# SCHEMATICS.net
KiCad netlist of a schematic drawn in Altium Designer
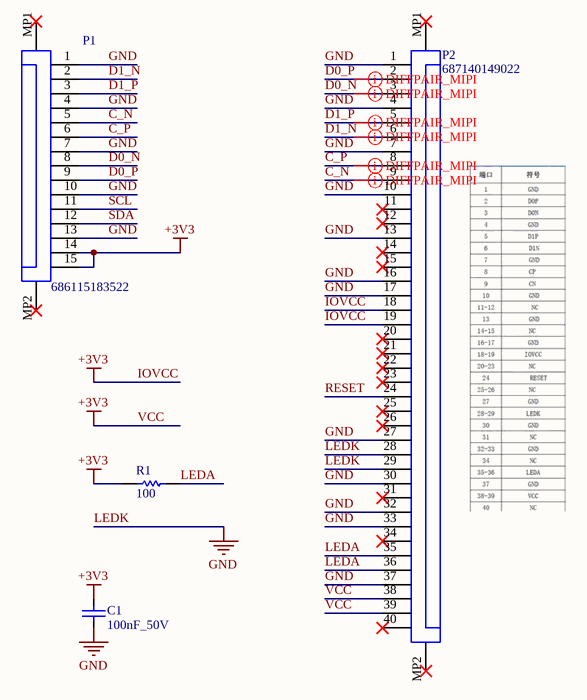
[diagram p0: SCHEMATICS.SchDoc]

(export (version "E")
  (design (tool "Eeschema 10.0.6"))
  (components
    (comp (ref "C1")
      (value "100nF_50V")
      (footprint "CustomLib-Package:C0805")
      (description "50V 100nF X7R ±10% 0805 Multilayer Ceramic Capacitors MLCC - SMD/SMT ROHS")
      (fields (field (name "MANUFACTURER") "YAGEO") (field (name "Comment") "CC0805KRX7R9BB104"))
      (libsource (lib "CustomLib-Package") (part "CAPACITOR"))
    )
    (comp (ref "P1")
      (value "686115183522")
      (footprint "686115183522")
      (description "15 Position FFC, FPC Connector Contacts, Bottom 1.0mm Surface Mount, Right Angle")
      (libsource (lib "CustomLib-Package") (part "CON-FPC-1MM-15P-RA"))
    )
    (comp (ref "P2")
      (value "687140149022")
      (footprint "687140149022")
      (description "40 Position FFC, FPC Connector Contacts, Bottom 0.020 (0.50mm) Surface Mount, Right Angle")
      (libsource (lib "CustomLib-Package") (part "CON-FPC-0.5MM-40P-RA"))
    )
    (comp (ref "R1")
      (value "100")
      (footprint "CustomLib-Package:R0805")
      (fields (field (name "MANUFACTURER") "YAGEO") (field (name "Comment") "AC0805FR-07100RL"))
      (libsource (lib "CustomLib-Package") (part "RESISTOR"))
    )
  )
  (nets
    (net (code "1") (name "+3V3") (class "Default")
      (node (ref "C1") (pin "1") (pinfunction "1_1") (pintype "passive"))
      (node (ref "P1") (pin "14") (pinfunction "14_14") (pintype "passive"))
      (node (ref "P1") (pin "15") (pinfunction "15_15") (pintype "passive"))
      (node (ref "P2") (pin "18") (pinfunction "18_18") (pintype "passive"))
      (node (ref "P2") (pin "19") (pinfunction "19_19") (pintype "passive"))
      (node (ref "P2") (pin "38") (pinfunction "38_38") (pintype "passive"))
      (node (ref "P2") (pin "39") (pinfunction "39_39") (pintype "passive"))
      (node (ref "R1") (pin "2") (pinfunction "2_2") (pintype "passive"))
    )
    (net (code "2") (name "/C_N") (class "Default")
      (node (ref "P1") (pin "5") (pinfunction "5_5") (pintype "passive"))
      (node (ref "P2") (pin "9") (pinfunction "9_9") (pintype "passive"))
    )
    (net (code "3") (name "/C_P") (class "Default")
      (node (ref "P1") (pin "6") (pinfunction "6_6") (pintype "passive"))
      (node (ref "P2") (pin "8") (pinfunction "8_8") (pintype "passive"))
    )
    (net (code "4") (name "/D0_N") (class "Default")
      (node (ref "P1") (pin "8") (pinfunction "8_8") (pintype "passive"))
      (node (ref "P2") (pin "3") (pinfunction "3_3") (pintype "passive"))
    )
    (net (code "5") (name "/D0_P") (class "Default")
      (node (ref "P1") (pin "9") (pinfunction "9_9") (pintype "passive"))
      (node (ref "P2") (pin "2") (pinfunction "2_2") (pintype "passive"))
    )
    (net (code "6") (name "/D1_N") (class "Default")
      (node (ref "P1") (pin "2") (pinfunction "2_2") (pintype "passive"))
      (node (ref "P2") (pin "6") (pinfunction "6_6") (pintype "passive"))
    )
    (net (code "7") (name "/D1_P") (class "Default")
      (node (ref "P1") (pin "3") (pinfunction "3_3") (pintype "passive"))
      (node (ref "P2") (pin "5") (pinfunction "5_5") (pintype "passive"))
    )
    (net (code "8") (name "/LEDA") (class "Default")
      (node (ref "P2") (pin "35") (pinfunction "35_35") (pintype "passive"))
      (node (ref "P2") (pin "36") (pinfunction "36_36") (pintype "passive"))
      (node (ref "R1") (pin "1") (pinfunction "1_1") (pintype "passive"))
    )
    (net (code "9") (name "/RESET") (class "Default")
      (node (ref "P2") (pin "24") (pinfunction "24_24") (pintype "passive"))
    )
    (net (code "10") (name "/SCL") (class "Default")
      (node (ref "P1") (pin "11") (pinfunction "11_11") (pintype "passive"))
    )
    (net (code "11") (name "/SDA") (class "Default")
      (node (ref "P1") (pin "12") (pinfunction "12_12") (pintype "passive"))
    )
    (net (code "12") (name "GND") (class "Default")
      (node (ref "C1") (pin "2") (pinfunction "2_2") (pintype "passive"))
      (node (ref "P1") (pin "1") (pinfunction "1_1") (pintype "passive"))
      (node (ref "P1") (pin "10") (pinfunction "10_10") (pintype "passive"))
      (node (ref "P1") (pin "13") (pinfunction "13_13") (pintype "passive"))
      (node (ref "P1") (pin "4") (pinfunction "4_4") (pintype "passive"))
      (node (ref "P1") (pin "7") (pinfunction "7_7") (pintype "passive"))
      (node (ref "P2") (pin "1") (pinfunction "1_1") (pintype "passive"))
      (node (ref "P2") (pin "10") (pinfunction "10_10") (pintype "passive"))
      (node (ref "P2") (pin "13") (pinfunction "13_13") (pintype "passive"))
      (node (ref "P2") (pin "16") (pinfunction "16_16") (pintype "passive"))
      (node (ref "P2") (pin "17") (pinfunction "17_17") (pintype "passive"))
      (node (ref "P2") (pin "27") (pinfunction "27_27") (pintype "passive"))
      (node (ref "P2") (pin "28") (pinfunction "28_28") (pintype "passive"))
      (node (ref "P2") (pin "29") (pinfunction "29_29") (pintype "passive"))
      (node (ref "P2") (pin "30") (pinfunction "30_30") (pintype "passive"))
      (node (ref "P2") (pin "32") (pinfunction "32_32") (pintype "passive"))
      (node (ref "P2") (pin "33") (pinfunction "33_33") (pintype "passive"))
      (node (ref "P2") (pin "37") (pinfunction "37_37") (pintype "passive"))
      (node (ref "P2") (pin "4") (pinfunction "4_4") (pintype "passive"))
      (node (ref "P2") (pin "7") (pinfunction "7_7") (pintype "passive"))
    )
    (net (code "13") (name "unconnected-(P1-PadMP1)") (class "Default")
      (node (ref "P1") (pin "MP1") (pinfunction "MP1_MP1") (pintype "passive+no_connect"))
    )
    (net (code "14") (name "unconnected-(P1-PadMP2)") (class "Default")
      (node (ref "P1") (pin "MP2") (pinfunction "MP2_MP2") (pintype "passive+no_connect"))
    )
    (net (code "15") (name "unconnected-(P2-Pad11)") (class "Default")
      (node (ref "P2") (pin "11") (pinfunction "11_11") (pintype "passive+no_connect"))
    )
    (net (code "16") (name "unconnected-(P2-Pad12)") (class "Default")
      (node (ref "P2") (pin "12") (pinfunction "12_12") (pintype "passive+no_connect"))
    )
    (net (code "17") (name "unconnected-(P2-Pad14)") (class "Default")
      (node (ref "P2") (pin "14") (pinfunction "14_14") (pintype "passive+no_connect"))
    )
    (net (code "18") (name "unconnected-(P2-Pad15)") (class "Default")
      (node (ref "P2") (pin "15") (pinfunction "15_15") (pintype "passive+no_connect"))
    )
    (net (code "19") (name "unconnected-(P2-Pad20)") (class "Default")
      (node (ref "P2") (pin "20") (pinfunction "20_20") (pintype "passive+no_connect"))
    )
    (net (code "20") (name "unconnected-(P2-Pad21)") (class "Default")
      (node (ref "P2") (pin "21") (pinfunction "21_21") (pintype "passive+no_connect"))
    )
    (net (code "21") (name "unconnected-(P2-Pad22)") (class "Default")
      (node (ref "P2") (pin "22") (pinfunction "22_22") (pintype "passive+no_connect"))
    )
    (net (code "22") (name "unconnected-(P2-Pad23)") (class "Default")
      (node (ref "P2") (pin "23") (pinfunction "23_23") (pintype "passive+no_connect"))
    )
    (net (code "23") (name "unconnected-(P2-Pad25)") (class "Default")
      (node (ref "P2") (pin "25") (pinfunction "25_25") (pintype "passive+no_connect"))
    )
    (net (code "24") (name "unconnected-(P2-Pad26)") (class "Default")
      (node (ref "P2") (pin "26") (pinfunction "26_26") (pintype "passive+no_connect"))
    )
    (net (code "25") (name "unconnected-(P2-Pad31)") (class "Default")
      (node (ref "P2") (pin "31") (pinfunction "31_31") (pintype "passive+no_connect"))
    )
    (net (code "26") (name "unconnected-(P2-Pad34)") (class "Default")
      (node (ref "P2") (pin "34") (pinfunction "34_34") (pintype "passive+no_connect"))
    )
    (net (code "27") (name "unconnected-(P2-Pad40)") (class "Default")
      (node (ref "P2") (pin "40") (pinfunction "40_40") (pintype "passive+no_connect"))
    )
    (net (code "28") (name "unconnected-(P2-PadMP1)") (class "Default")
      (node (ref "P2") (pin "MP1") (pinfunction "MP1_MP1") (pintype "passive+no_connect"))
    )
    (net (code "29") (name "unconnected-(P2-PadMP2)") (class "Default")
      (node (ref "P2") (pin "MP2") (pinfunction "MP2_MP2") (pintype "passive+no_connect"))
    )
  )
)
